# 24Vto320V.net
KiCad netlist of a schematic drawn in Altium Designer
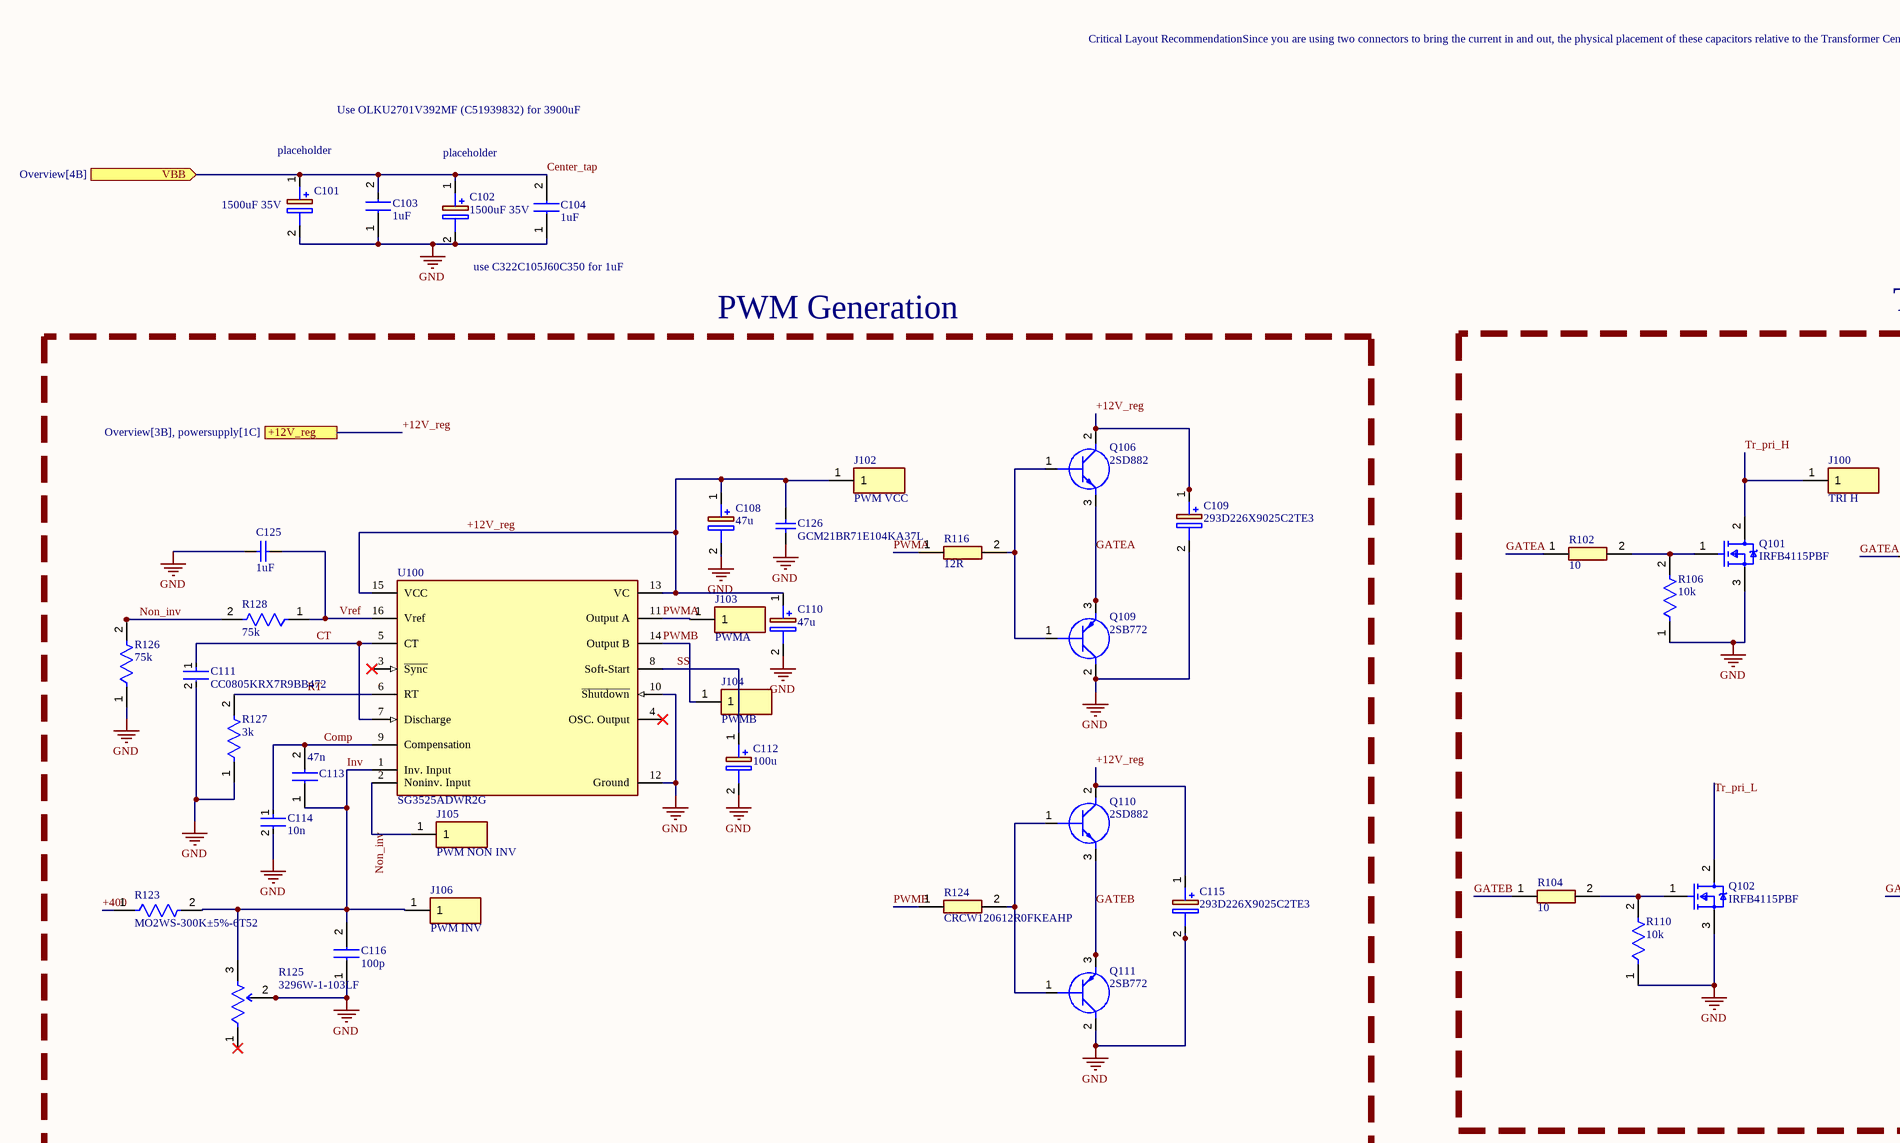
[diagram p0: 24Vto320V.SchDoc, top left]
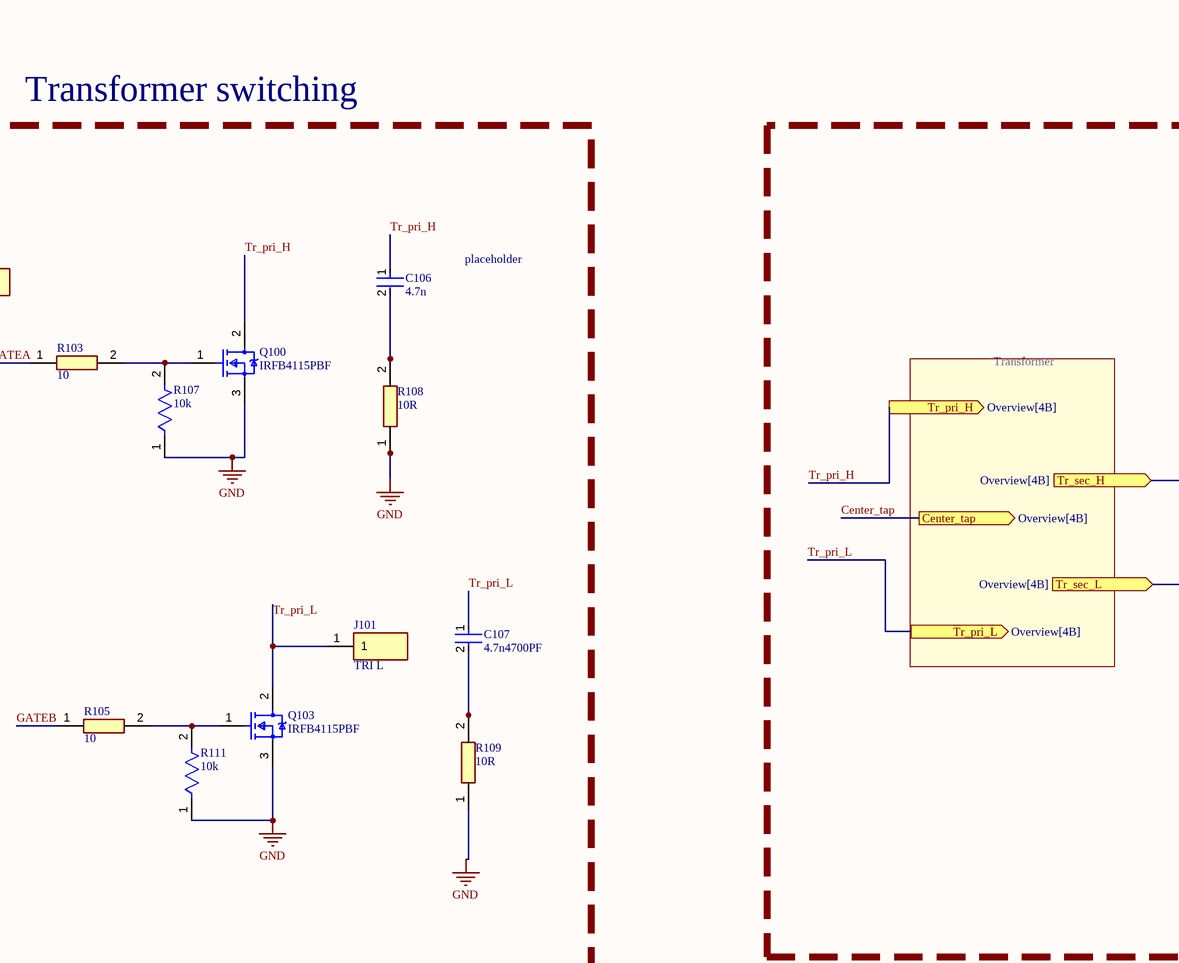
[diagram p1: 24Vto320V.SchDoc, top middle]
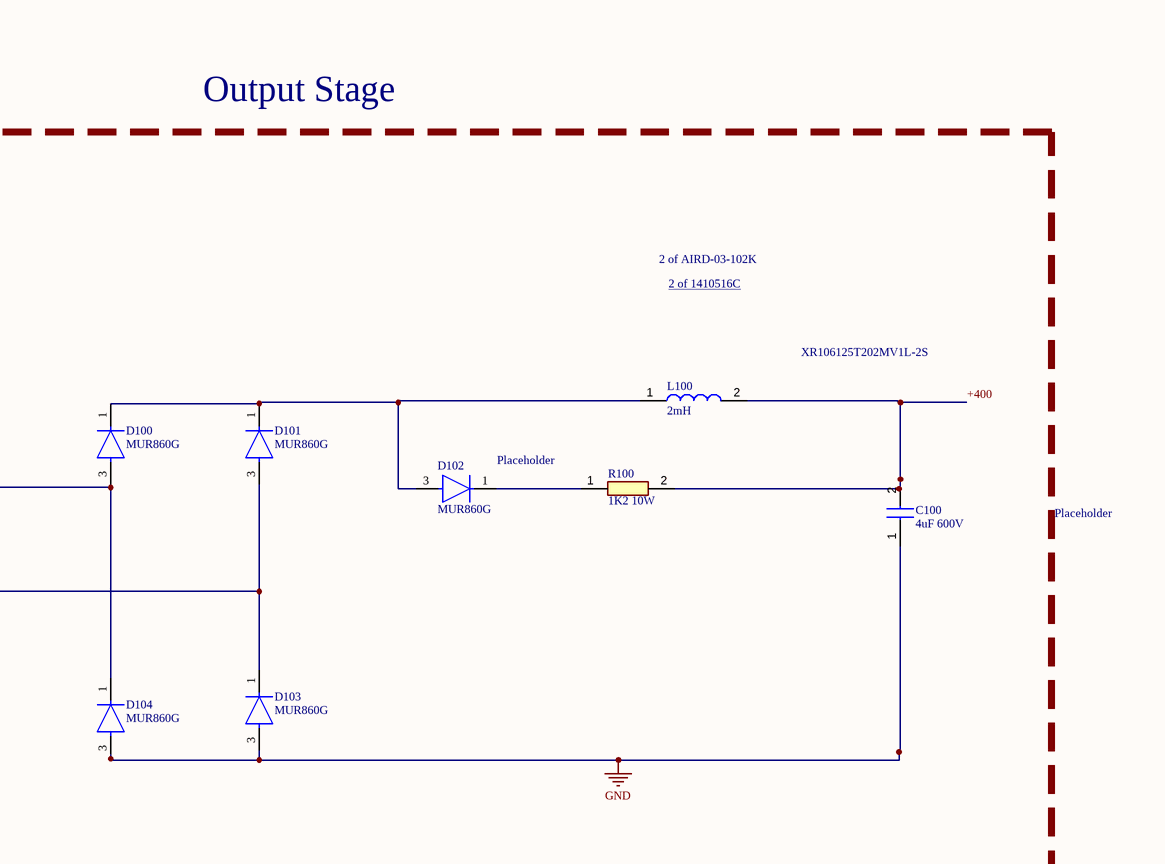
[diagram p2: 24Vto320V.SchDoc, top right]
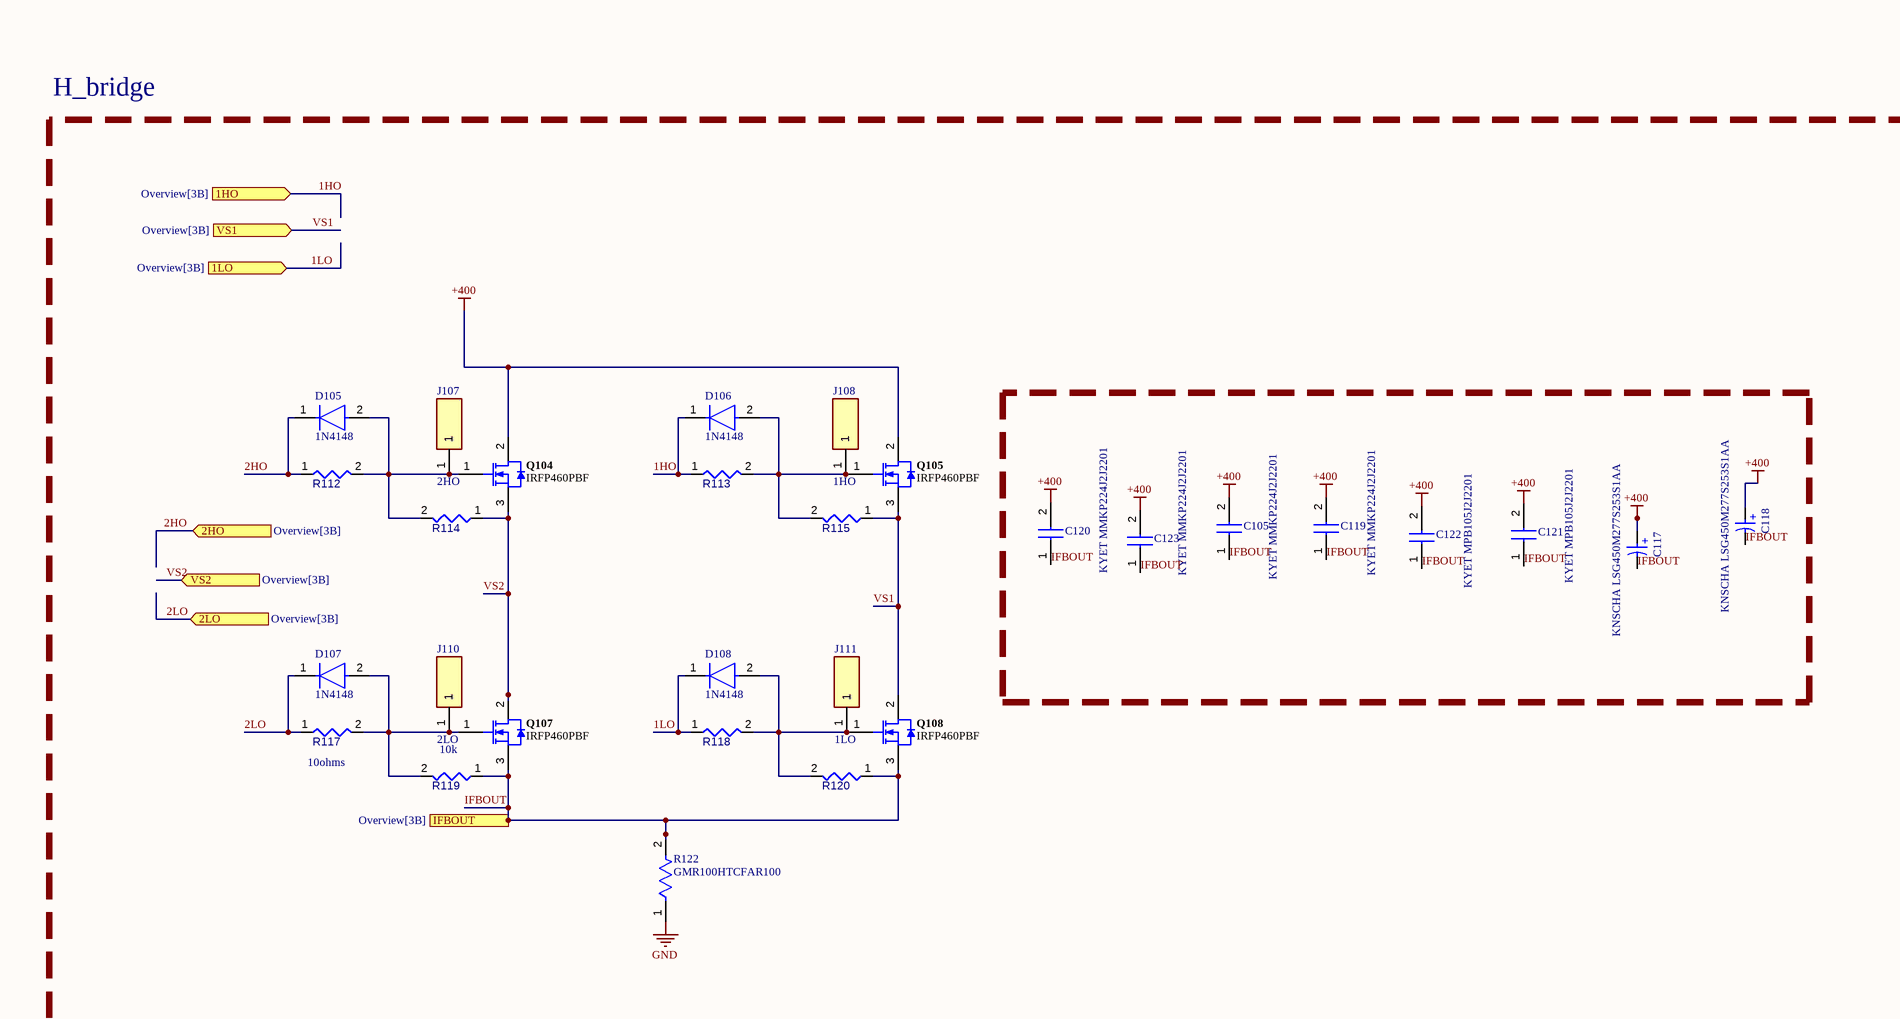
[diagram p3: 24Vto320V.SchDoc, bottom left]
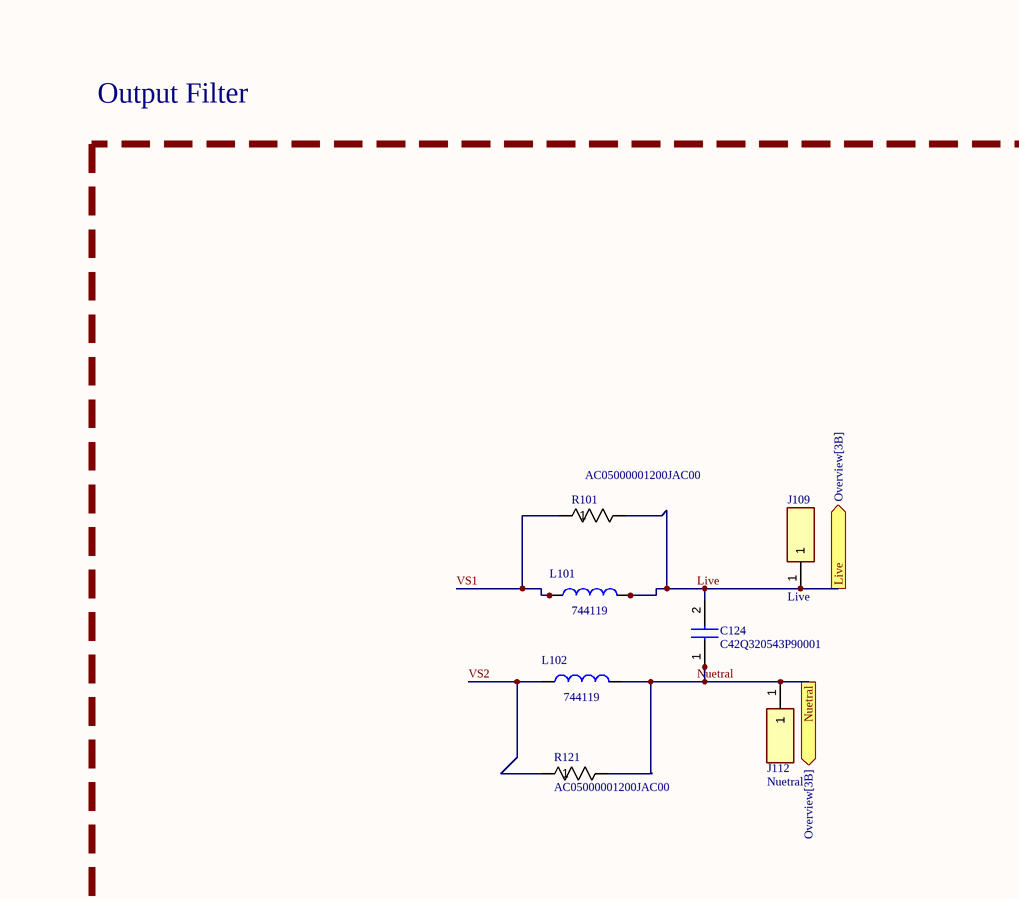
[diagram p4: 24Vto320V.SchDoc, bottom middle]

(export (version "E")
  (design (tool "Eeschema 10.0.6"))
  (components
    (comp (ref "C100")
      (value "4uF 600V")
      (footprint "SamacSys:ECWFE2J225P5")
      (description "C3D1U405KB00C00")
      (fields (field (name "MANUFACTURER_PART_NUMBER") "ECW-FE2J225P5"))
      (libsource (lib "SamacSys") (part "ECW-FE2J225P5"))
    )
    (comp (ref "C101")
      (value "1500uF 35V")
      (footprint "SamacSys:CAPPRD750W85D1800H2200")
      (description "35ZLH1500MEFC12.5X30")
      (fields
        (field (name "MANUFACTURER_PART_NUMBER") "EEU-FC1V152S")
        (field (name "MOUSER PART NUMBER") "667-EEU-FC1V152S")
      )
      (libsource (lib "*") (part "EEU-FC1V152S"))
    )
    (comp (ref "C102")
      (value "1500uF 35V")
      (footprint "SamacSys:CAPPRD750W85D1800H2200")
      (description "35ZLH1500MEFC12.5X30")
      (fields
        (field (name "MANUFACTURER_PART_NUMBER") "EEU-FC1V152S")
        (field (name "MOUSER PART NUMBER") "667-EEU-FC1V152S")
      )
      (libsource (lib "*") (part "EEU-FC1V152S"))
    )
    (comp (ref "C103")
      (value "1uF")
      (footprint "SamacSys:R75IN41004040J")
      (description "C322C105J60C350")
      (fields
        (field (name "MANUFACTURER_PART_NUMBER") "R75IN41004040J")
        (field (name "MOUSER PART NUMBER") "80-R75IN41004040J")
      )
      (libsource (lib "*") (part "R75IN41004040J"))
    )
    (comp (ref "C104")
      (value "1uF")
      (footprint "SamacSys:R75IN41004040J")
      (description "C322C105J60C350")
      (fields
        (field (name "MANUFACTURER_PART_NUMBER") "R75IN41004040J")
        (field (name "MOUSER PART NUMBER") "80-R75IN41004040J")
      )
      (libsource (lib "*") (part "R75IN41004040J"))
    )
    (comp (ref "C105")
      (value "KYET MMKP224J2J2201")
      (footprint "222233915224")
      (description "220nF Film Capacitor ±5% 630V Through Hole P=22.5mm")
      (fields (field (name "MANUFACTURER_PART_NUMBER") "222233915224"))
      (libsource (lib "myComponents") (part "222233915224"))
    )
    (comp (ref "C106")
      (value "4.7n")
      (footprint "FP-C1206C-EB-MFG")
      (description "CAP CER 4700PF 100V 10% X7R 1206\r\nCC1206KRX7R0BB472")
      (fields
        (field (name "TOLERANCE") "0.1")
        (field (name "OCTOPART") "https://octopart.com/c1206c472k1ractu-kemet-3865440")
      )
      (libsource (lib "Altium Content Vault") (part "b4654b650e69147ec39a6b967a45e02"))
    )
    (comp (ref "C107")
      (value "4.7n4700PF")
      (footprint "FP-C1206C-EB-MFG")
      (description "CAP CER 4700PF 100V 10% X7R 1206\r\nCC1206KRX7R0BB472")
      (fields
        (field (name "TOLERANCE") "0.1")
        (field (name "OCTOPART") "https://octopart.com/c1206c472k1ractu-kemet-3865440")
      )
      (libsource (lib "Altium Content Vault") (part "b4654b650e69147ec39a6b967a45e02"))
    )
    (comp (ref "C108")
      (value "47u")
      (footprint "SamacSys:CAPPRD250W55D655H1220")
      (description "EEU-FC1V470")
      (fields (field (name "MOUSER PART NUMBER") "667-EEU-FC1V470"))
      (libsource (lib "*") (part "EEU-FC1V470"))
    )
    (comp (ref "C109")
      (value "293D226X9025C2TE3")
      (footprint "CAPPM6032X280N")
      (description "Capacitor Polarised")
      (fields (field (name "MOUSER PART NUMBER") "74-293D226X9025C2TE3"))
      (libsource (lib "myComponents") (part "293D226X9025C2TE3"))
    )
    (comp (ref "C110")
      (value "47u")
      (footprint "SamacSys:CAPPRD250W55D655H1220")
      (description "EEU-FC1V470")
      (fields (field (name "MOUSER PART NUMBER") "667-EEU-FC1V470"))
      (libsource (lib "*") (part "EEU-FC1V470"))
    )
    (comp (ref "C111")
      (value "CC0805KRX7R9BB472")
      (footprint "FP-CC0805-0_85-MFG")
      (description "CAP CER 4700PF 50V X7R 0805")
      (fields (field (name "TOLERANCE") "0.1") (field (name "MANUFACTURER") "Yageo"))
      (libsource (lib "Altium Content Vault") (part "11868f565c42a9108669ba33697ecf6"))
    )
    (comp (ref "C112")
      (value "100u")
      (footprint "SamacSys:EEE0JA331XP")
      (description "EEE-1VA101XP")
      (fields (field (name "MOUSER PART NUMBER") "667-EEE-1VA101XP"))
      (libsource (lib "*") (part "EEE-1VA101XP"))
    )
    (comp (ref "C113")
      (value "47n")
      (footprint "SamacSys:CAPC2012X145N")
      (description "GRM21BR71H473KA01L")
      (fields (field (name "MOUSER PART NUMBER") "81-GRM40X473K50L"))
      (libsource (lib "*") (part "GRM21BR71H473KA01L"))
    )
    (comp (ref "C114")
      (value "10n")
      (footprint "FP-CC0805-0_85-MFG")
      (description "CAP CER 10000PF 50V X7R 0805\r\nCC0805KRX7R9BB103")
      (fields
        (field (name "OCTOPART") "https://octopart.com/cc0805krx7r9bb103-yageo-192989")
        (field (name "MANUFACTURER") "Yageo")
      )
      (libsource (lib "Altium Content Vault") (part "11868f565c42a9108669ba33697ecf6"))
    )
    (comp (ref "C115")
      (value "293D226X9025C2TE3")
      (footprint "CAPPM6032X280N")
      (description "Capacitor Polarised")
      (fields (field (name "MOUSER PART NUMBER") "74-293D226X9025C2TE3"))
      (libsource (lib "myComponents") (part "293D226X9025C2TE3"))
    )
    (comp (ref "C116")
      (value "100p")
      (footprint "SamacSys:CAPC3216X88N")
      (description "C1206C101J5GACTU7990")
      (libsource (lib "*") (part "C1206C101J5GACTU7990"))
    )
    (comp (ref "C117")
      (value "KNSCHA LSG450M277S253S1AA")
      (footprint "WCAP-AIG8_D30H30")
      (description "270uF ±20% 450V Aluminum Electrolytic Capacitors Through Hole,D30xL25mm")
      (fields (field (name "TOLERANCE") "20%"))
      (libsource (lib "Altium Content Vault") (part "Capacitor_Polarized"))
    )
    (comp (ref "C118")
      (value "KNSCHA LSG450M277S253S1AA")
      (footprint "WCAP-AIG8_D30H30")
      (description "270uF ±20% 450V Aluminum Electrolytic Capacitors Through Hole,D30xL25mm")
      (fields (field (name "TOLERANCE") "20%"))
      (libsource (lib "Altium Content Vault") (part "Capacitor_Polarized"))
    )
    (comp (ref "C119")
      (value "KYET MMKP224J2J2201")
      (footprint "222233915224")
      (description "220nF Film Capacitor ±5% 630V Through Hole P=22.5mm")
      (fields (field (name "MANUFACTURER_PART_NUMBER") "222233915224"))
      (libsource (lib "myComponents") (part "222233915224"))
    )
    (comp (ref "C120")
      (value "KYET MMKP224J2J2201")
      (footprint "222233915224")
      (description "220nF Film Capacitor ±5% 630V Through Hole P=22.5mm")
      (fields (field (name "MANUFACTURER_PART_NUMBER") "222233915224"))
      (libsource (lib "myComponents") (part "222233915224"))
    )
    (comp (ref "C121")
      (value "KYET MPB105J2J2201")
      (footprint "222233915224")
      (description "1uF Film Capacitor ±5% 630V Through Hole P=22.5mm")
      (fields (field (name "MANUFACTURER_PART_NUMBER") "222233915224"))
      (libsource (lib "myComponents") (part "222233915224"))
    )
    (comp (ref "C122")
      (value "KYET MPB105J2J2201")
      (footprint "222233915224")
      (description "1uF Film Capacitor ±5% 630V Through Hole P=22.5mm")
      (fields (field (name "MANUFACTURER_PART_NUMBER") "222233915224"))
      (libsource (lib "myComponents") (part "222233915224"))
    )
    (comp (ref "C123")
      (value "KYET MMKP224J2J2201")
      (footprint "222233915224")
      (description "220nF Film Capacitor ±5% 630V Through Hole P=22.5mm")
      (fields (field (name "MANUFACTURER_PART_NUMBER") "222233915224"))
      (libsource (lib "myComponents") (part "222233915224"))
    )
    (comp (ref "C124")
      (value "C42Q320543P90001")
      (footprint "222233915224")
      (description "2uF ±10% 275V 310V Safety Capacitor X2 Through Hole,P=22.5mm")
      (fields (field (name "MANUFACTURER_PART_NUMBER") "222233915224"))
      (libsource (lib "myComponents") (part "222233915224"))
    )
    (comp (ref "C125")
      (value "1uF")
      (footprint "CAPC2013X140X50LL20T25")
      (description "C0805C105K3RACTU")
      (fields (field (name "MANUFACTURER") "Kemet"))
      (libsource (lib "Altium Content Vault") (part "CAP"))
    )
    (comp (ref "C126")
      (value "GCM21BR71E104KA37L")
      (footprint "CAPC2013X140X45LL15T25")
      (fields (field (name "MANUFACTURER") "Murata"))
      (libsource (lib "Altium Content Vault") (part "CAP"))
    )
    (comp (ref "D100")
      (value "MUR860G")
      (footprint "FP-221B-04-MFG")
      (libsource (lib "Altium Content Vault") (part "40f15f7c8986038b0a9b2b5fe848ef9"))
    )
    (comp (ref "D101")
      (value "MUR860G")
      (footprint "FP-221B-04-MFG")
      (libsource (lib "Altium Content Vault") (part "40f15f7c8986038b0a9b2b5fe848ef9"))
    )
    (comp (ref "D102")
      (value "MUR860G")
      (footprint "FP-221B-04-MFG")
      (libsource (lib "Altium Content Vault") (part "40f15f7c8986038b0a9b2b5fe848ef9"))
    )
    (comp (ref "D103")
      (value "MUR860G")
      (footprint "FP-221B-04-MFG")
      (libsource (lib "Altium Content Vault") (part "40f15f7c8986038b0a9b2b5fe848ef9"))
    )
    (comp (ref "D104")
      (value "MUR860G")
      (footprint "FP-221B-04-MFG")
      (libsource (lib "Altium Content Vault") (part "40f15f7c8986038b0a9b2b5fe848ef9"))
    )
    (comp (ref "D105")
      (value "1N4148")
      (footprint "FP-017AG-MFG")
      (description "DIODE GEN PURP 100V 200MA DO35")
      (fields (field (name "VOLTAGE") "100V"))
      (libsource (lib "Altium Content Vault") (part "d7152d700b627762746794eb795d46e"))
    )
    (comp (ref "D106")
      (value "1N4148")
      (footprint "FP-017AG-MFG")
      (description "DIODE GEN PURP 100V 200MA DO35")
      (fields (field (name "VOLTAGE") "100V"))
      (libsource (lib "Altium Content Vault") (part "d7152d700b627762746794eb795d46e"))
    )
    (comp (ref "D107")
      (value "1N4148")
      (footprint "FP-017AG-MFG")
      (description "DIODE GEN PURP 100V 200MA DO35")
      (fields (field (name "VOLTAGE") "100V"))
      (libsource (lib "Altium Content Vault") (part "d7152d700b627762746794eb795d46e"))
    )
    (comp (ref "D108")
      (value "1N4148")
      (footprint "FP-017AG-MFG")
      (description "DIODE GEN PURP 100V 200MA DO35")
      (fields (field (name "VOLTAGE") "100V"))
      (libsource (lib "Altium Content Vault") (part "d7152d700b627762746794eb795d46e"))
    )
    (comp (ref "J100")
      (value "TRI H")
      (footprint "5000")
      (description "Connector")
      (fields (field (name "MANUFACTURER_PART_NUMBER") "5000") (field (name "MOUSER PART NUMBER") "534-5000"))
      (libsource (lib "myComponents") (part "5000"))
    )
    (comp (ref "J101")
      (value "TRI L")
      (footprint "5000")
      (description "Connector")
      (fields (field (name "MANUFACTURER_PART_NUMBER") "5000") (field (name "MOUSER PART NUMBER") "534-5000"))
      (libsource (lib "myComponents") (part "5000"))
    )
    (comp (ref "J102")
      (value "PWM VCC")
      (footprint "5000")
      (description "Connector")
      (fields (field (name "MANUFACTURER_PART_NUMBER") "5000") (field (name "MOUSER PART NUMBER") "534-5000"))
      (libsource (lib "myComponents") (part "5000"))
    )
    (comp (ref "J103")
      (value "PWMA")
      (footprint "5000")
      (description "Connector")
      (fields (field (name "MANUFACTURER_PART_NUMBER") "5000") (field (name "MOUSER PART NUMBER") "534-5000"))
      (libsource (lib "myComponents") (part "5000"))
    )
    (comp (ref "J104")
      (value "PWMB")
      (footprint "5000")
      (description "Connector")
      (fields (field (name "MANUFACTURER_PART_NUMBER") "5000") (field (name "MOUSER PART NUMBER") "534-5000"))
      (libsource (lib "myComponents") (part "5000"))
    )
    (comp (ref "J105")
      (value "PWM NON INV")
      (footprint "5000")
      (description "Connector")
      (fields (field (name "MANUFACTURER_PART_NUMBER") "5000") (field (name "MOUSER PART NUMBER") "534-5000"))
      (libsource (lib "myComponents") (part "5000"))
    )
    (comp (ref "J106")
      (value "PWM INV")
      (footprint "5000")
      (description "Connector")
      (fields (field (name "MANUFACTURER_PART_NUMBER") "5000") (field (name "MOUSER PART NUMBER") "534-5000"))
      (libsource (lib "myComponents") (part "5000"))
    )
    (comp (ref "J107")
      (value "2HO")
      (footprint "5000")
      (description "Connector")
      (fields (field (name "MANUFACTURER_PART_NUMBER") "5000") (field (name "MOUSER PART NUMBER") "534-5000"))
      (libsource (lib "") (part "5000_1"))
    )
    (comp (ref "J108")
      (value "1HO")
      (footprint "5000")
      (description "Connector")
      (fields (field (name "MANUFACTURER_PART_NUMBER") "5000") (field (name "MOUSER PART NUMBER") "534-5000"))
      (libsource (lib "") (part "5000_1"))
    )
    (comp (ref "J109")
      (value "Live")
      (footprint "5000")
      (description "Connector")
      (fields (field (name "MANUFACTURER_PART_NUMBER") "5000") (field (name "MOUSER PART NUMBER") "534-5000"))
      (libsource (lib "") (part "5000_1"))
    )
    (comp (ref "J110")
      (value "2LO")
      (footprint "5000")
      (description "Connector")
      (fields (field (name "MANUFACTURER_PART_NUMBER") "5000") (field (name "MOUSER PART NUMBER") "534-5000"))
      (libsource (lib "") (part "5000_1"))
    )
    (comp (ref "J111")
      (value "1LO")
      (footprint "5000")
      (description "Connector")
      (fields (field (name "MANUFACTURER_PART_NUMBER") "5000") (field (name "MOUSER PART NUMBER") "534-5000"))
      (libsource (lib "") (part "5000_1"))
    )
    (comp (ref "J112")
      (value "Nuetral")
      (footprint "5000")
      (description "Connector")
      (fields (field (name "MANUFACTURER_PART_NUMBER") "5000") (field (name "MOUSER PART NUMBER") "534-5000"))
      (libsource (lib "") (part "5000_2"))
    )
    (comp (ref "L100")
      (value "2mH")
      (footprint "SamacSys:2300LL102VRC")
      (description "XR106125T202MV1L-2S")
      (fields
        (field (name "MANUFACTURER_PART_NUMBER") "2300LL-102-V-RC")
        (field (name "MOUSER PART NUMBER") "652-2300LL-102-V-RC")
      )
      (libsource (lib "*") (part "2300LL-102-V-RC"))
    )
    (comp (ref "L101")
      (value "744119")
      (footprint "744119")
      (description "Toroidal Inductor, 890Uh, 2A, Tht Rohs Compliant: Yes")
      (fields (field (name "TOLERANCE") "20%"))
      (libsource (lib "Altium Content Vault") (part "Inductor - 1"))
    )
    (comp (ref "L102")
      (value "744119")
      (footprint "744119")
      (description "Toroidal Inductor, 890Uh, 2A, Tht Rohs Compliant: Yes")
      (fields (field (name "TOLERANCE") "20%"))
      (libsource (lib "Altium Content Vault") (part "Inductor - 1"))
    )
    (comp (ref "Q100")
      (value "IRFB4115PBF")
      (footprint "FP-PG-TO220-3-MFG")
      (description "MOSFET N-CH 150V 104A TO220AB")
      (fields
        (field (name "OCTOPART") "https://octopart.com/irfb4115pbf-infineon-65873822")
        (field (name "MANUFACTURER") "Infineon Technologies")
      )
      (libsource (lib "Altium Content Vault") (part "b09f7f152735e370c1ea22a33fa83d6"))
    )
    (comp (ref "Q101")
      (value "IRFB4115PBF")
      (footprint "FP-PG-TO220-3-MFG")
      (description "MOSFET N-CH 150V 104A TO220AB")
      (fields
        (field (name "OCTOPART") "https://octopart.com/irfb4115pbf-infineon-65873822")
        (field (name "MANUFACTURER") "Infineon Technologies")
      )
      (libsource (lib "Altium Content Vault") (part "b09f7f152735e370c1ea22a33fa83d6"))
    )
    (comp (ref "Q102")
      (value "IRFB4115PBF")
      (footprint "FP-PG-TO220-3-MFG")
      (description "MOSFET N-CH 150V 104A TO220AB")
      (fields
        (field (name "OCTOPART") "https://octopart.com/irfb4115pbf-infineon-65873822")
        (field (name "MANUFACTURER") "Infineon Technologies")
      )
      (libsource (lib "Altium Content Vault") (part "b09f7f152735e370c1ea22a33fa83d6"))
    )
    (comp (ref "Q103")
      (value "IRFB4115PBF")
      (footprint "FP-PG-TO220-3-MFG")
      (description "MOSFET N-CH 150V 104A TO220AB")
      (fields
        (field (name "OCTOPART") "https://octopart.com/irfb4115pbf-infineon-65873822")
        (field (name "MANUFACTURER") "Infineon Technologies")
      )
      (libsource (lib "Altium Content Vault") (part "b09f7f152735e370c1ea22a33fa83d6"))
    )
    (comp (ref "Q104")
      (value "IRFP460PBF")
      (footprint "VISH-TO-247AC-3")
      (description "N-Channel Power MOSFET, 500 V, -55 to 150 degC, 3-Pin FM (TO-247), RoHS, Tube")
      (fields (field (name "MANUFACTURER") "Vishay"))
      (libsource (lib "Altium Content Vault") (part "NEMOS-GDS-3"))
    )
    (comp (ref "Q105")
      (value "IRFP460PBF")
      (footprint "VISH-TO-247AC-3")
      (description "N-Channel Power MOSFET, 500 V, -55 to 150 degC, 3-Pin FM (TO-247), RoHS, Tube")
      (fields (field (name "MANUFACTURER") "Vishay"))
      (libsource (lib "Altium Content Vault") (part "NEMOS-GDS-3"))
    )
    (comp (ref "Q106")
      (value "2SD882")
      (footprint "SamacSys:BD235")
      (description "Transistor BJT NPN")
      (fields (field (name "MOUSER PART NUMBER") "511-2SD882"))
      (libsource (lib "*") (part "2SD882"))
    )
    (comp (ref "Q107")
      (value "IRFP460PBF")
      (footprint "VISH-TO-247AC-3")
      (description "N-Channel Power MOSFET, 500 V, -55 to 150 degC, 3-Pin FM (TO-247), RoHS, Tube")
      (fields (field (name "MANUFACTURER") "Vishay"))
      (libsource (lib "Altium Content Vault") (part "NEMOS-GDS-3"))
    )
    (comp (ref "Q108")
      (value "IRFP460PBF")
      (footprint "VISH-TO-247AC-3")
      (description "N-Channel Power MOSFET, 500 V, -55 to 150 degC, 3-Pin FM (TO-247), RoHS, Tube")
      (fields (field (name "MANUFACTURER") "Vishay"))
      (libsource (lib "Altium Content Vault") (part "NEMOS-GDS-3"))
    )
    (comp (ref "Q109")
      (value "2SB772")
      (footprint "SamacSys:TO229P290X760X1320-3P")
      (description "Transistor BJT PNP")
      (fields (field (name "MOUSER PART NUMBER") "511-2SB772"))
      (libsource (lib "*") (part "2SB772"))
    )
    (comp (ref "Q110")
      (value "2SD882")
      (footprint "SamacSys:BD235")
      (description "Transistor BJT NPN")
      (fields (field (name "MOUSER PART NUMBER") "511-2SD882"))
      (libsource (lib "*") (part "2SD882"))
    )
    (comp (ref "Q111")
      (value "2SB772")
      (footprint "SamacSys:TO229P290X760X1320-3P")
      (description "Transistor BJT PNP")
      (fields (field (name "MOUSER PART NUMBER") "511-2SB772"))
      (libsource (lib "*") (part "2SB772"))
    )
    (comp (ref "R100")
      (value "1K2 10W")
      (footprint "SamacSys:SQP10AJB100R")
      (description "SQP10AJB-1K2")
      (fields (field (name "MOUSER PART NUMBER") "603-SQP10AJB-1K2"))
      (libsource (lib "*") (part "SQP10AJB-1K2"))
    )
    (comp (ref "R101")
      (value "AC05000001200JAC00")
      (footprint "RES_AC05_VIS")
      (description "AC05000001200JAC00 Resistor, 120 Ohm, ± 5%, 5 W, Axial Leaded, Wirewound, General Purpose")
      (fields (field (name "TOLERANCE") "5%"))
      (libsource (lib "Altium Content Vault") (part "AC05000001200JAC00"))
    )
    (comp (ref "R102")
      (value "10")
      (footprint "SamacSys:RESC3216X60N")
      (description "CRCW120610R0FKEA")
      (fields (field (name "MOUSER PART NUMBER") "71-CRCW1206-10-E3"))
      (libsource (lib "*") (part "CRCW120610R0FKEA"))
    )
    (comp (ref "R103")
      (value "10")
      (footprint "SamacSys:RESC3216X60N")
      (description "CRCW120610R0FKEA")
      (fields (field (name "MOUSER PART NUMBER") "71-CRCW1206-10-E3"))
      (libsource (lib "*") (part "CRCW120610R0FKEA"))
    )
    (comp (ref "R104")
      (value "10")
      (footprint "SamacSys:RESC3216X60N")
      (description "CRCW120610R0FKEA")
      (fields (field (name "MOUSER PART NUMBER") "71-CRCW1206-10-E3"))
      (libsource (lib "*") (part "CRCW120610R0FKEA"))
    )
    (comp (ref "R105")
      (value "10")
      (footprint "SamacSys:RESC3216X60N")
      (description "CRCW120610R0FKEA")
      (fields (field (name "MOUSER PART NUMBER") "71-CRCW1206-10-E3"))
      (libsource (lib "*") (part "CRCW120610R0FKEA"))
    )
    (comp (ref "R106")
      (value "10k")
      (footprint "FP-CRCW0805-e3-IPC_A")
      (description "RES Thick Film, 10kΩ, 1%, 0.125W, 100ppm/°C, 0805, CRCW080510K0FKEA")
      (fields (field (name "TOLERANCE") "1%"))
      (libsource (lib "Altium Content Vault") (part "1029c3af85768c4190bb7ad29bc67b5"))
    )
    (comp (ref "R107")
      (value "10k")
      (footprint "FP-CRCW0805-e3-IPC_A")
      (description "RES Thick Film, 10kΩ, 1%, 0.125W, 100ppm/°C, 0805, CRCW080510K0FKEA")
      (fields (field (name "TOLERANCE") "1%"))
      (libsource (lib "Altium Content Vault") (part "1029c3af85768c4190bb7ad29bc67b5"))
    )
    (comp (ref "R108")
      (value "10R")
      (footprint "SamacSys:RESC6332X70N")
      (description "CRCW251210R0FKEG")
      (fields (field (name "MOUSER PART NUMBER") "71-CRCW2512-10-E3"))
      (libsource (lib "*") (part "CRCW251210R0FKEG"))
    )
    (comp (ref "R109")
      (value "10R")
      (footprint "SamacSys:RESC6332X70N")
      (description "CRCW251210R0FKEG")
      (fields (field (name "MOUSER PART NUMBER") "71-CRCW2512-10-E3"))
      (libsource (lib "*") (part "CRCW251210R0FKEG"))
    )
    (comp (ref "R110")
      (value "10k")
      (footprint "FP-CRCW0805-e3-IPC_A")
      (description "RES Thick Film, 10kΩ, 1%, 0.125W, 100ppm/°C, 0805, CRCW080510K0FKEA")
      (fields (field (name "TOLERANCE") "1%"))
      (libsource (lib "Altium Content Vault") (part "1029c3af85768c4190bb7ad29bc67b5"))
    )
    (comp (ref "R111")
      (value "10k")
      (footprint "FP-CRCW0805-e3-IPC_A")
      (description "RES Thick Film, 10kΩ, 1%, 0.125W, 100ppm/°C, 0805, CRCW080510K0FKEA")
      (fields (field (name "TOLERANCE") "1%"))
      (libsource (lib "Altium Content Vault") (part "1029c3af85768c4190bb7ad29bc67b5"))
    )
    (comp (ref "R112")
      (value "4.7 Ohm")
      (footprint "RESC0805(2012)_L")
      (description "4.7 Ohm 0.125W 5% 0805 (2012 Metric)  SMD")
      (fields (field (name "TOLERANCE") "5%") (field (name "POWER") "125mW"))
      (libsource (lib "Rahulb 23") (part "470R5J"))
    )
    (comp (ref "R113")
      (value "4.7 Ohm")
      (footprint "RESC0805(2012)_L")
      (description "4.7 Ohm 0.125W 5% 0805 (2012 Metric)  SMD")
      (fields (field (name "TOLERANCE") "5%") (field (name "POWER") "125mW"))
      (libsource (lib "Rahulb 23") (part "470R5J"))
    )
    (comp (ref "R114")
      (value "Resistor 10k +/-1% 0805 125 mW")
      (footprint "RESC2013X50X35ML15T15")
      (description "Chip Resistor, 10 KOhm, +/- 1%, 125 mW, -55 to 155 degC, 0805 (2012 Metric)")
      (fields (field (name "TOLERANCE") "1%") (field (name "POWER") "125mW"))
      (libsource (lib "Rahulb 23") (part "RES-2"))
    )
    (comp (ref "R115")
      (value "Resistor 10k +/-1% 0805 125 mW")
      (footprint "RESC2013X50X35ML15T15")
      (description "Chip Resistor, 10 KOhm, +/- 1%, 125 mW, -55 to 155 degC, 0805 (2012 Metric)")
      (fields (field (name "TOLERANCE") "1%") (field (name "POWER") "125mW"))
      (libsource (lib "Rahulb 23") (part "RES-2"))
    )
    (comp (ref "R116")
      (value "12R")
      (footprint "SamacSys:RESC3116X65N")
      (description "CRCW120612R0FKEAHP")
      (fields (field (name "MOUSER PART NUMBER") "71-CRCW120612R0FKEAH"))
      (libsource (lib "*") (part "CRCW120612R0FKEAHP"))
    )
    (comp (ref "R117")
      (value "4.7 Ohm")
      (footprint "RESC0805(2012)_L")
      (description "4.7 Ohm 0.125W 5% 0805 (2012 Metric)  SMD")
      (fields (field (name "TOLERANCE") "5%") (field (name "POWER") "125mW"))
      (libsource (lib "Rahulb 23") (part "470R5J"))
    )
    (comp (ref "R118")
      (value "4.7 Ohm")
      (footprint "RESC0805(2012)_L")
      (description "4.7 Ohm 0.125W 5% 0805 (2012 Metric)  SMD")
      (fields (field (name "TOLERANCE") "5%") (field (name "POWER") "125mW"))
      (libsource (lib "Rahulb 23") (part "470R5J"))
    )
    (comp (ref "R119")
      (value "Resistor 10k +/-1% 0805 125 mW")
      (footprint "RESC2013X50X35ML15T15")
      (description "Chip Resistor, 10 KOhm, +/- 1%, 125 mW, -55 to 155 degC, 0805 (2012 Metric)")
      (fields (field (name "TOLERANCE") "1%") (field (name "POWER") "125mW"))
      (libsource (lib "Rahulb 23") (part "RES-2"))
    )
    (comp (ref "R120")
      (value "Resistor 10k +/-1% 0805 125 mW")
      (footprint "RESC2013X50X35ML15T15")
      (description "Chip Resistor, 10 KOhm, +/- 1%, 125 mW, -55 to 155 degC, 0805 (2012 Metric)")
      (fields (field (name "TOLERANCE") "1%") (field (name "POWER") "125mW"))
      (libsource (lib "Rahulb 23") (part "RES-2"))
    )
    (comp (ref "R121")
      (value "AC05000001200JAC00")
      (footprint "RES_AC05_VIS")
      (description "AC05000001200JAC00 Resistor, 120 Ohm, ± 5%, 5 W, Axial Leaded, Wirewound, General Purpose")
      (fields (field (name "TOLERANCE") "5%"))
      (libsource (lib "Altium Content Vault") (part "AC05000001200JAC00"))
    )
    (comp (ref "R122")
      (value "GMR100HTCFAR100")
      (footprint "FP-GMR100-MFG")
      (description "RES 0.1 OHM 1% 7W 2512")
      (fields (field (name "TOLERANCE") "1%"))
      (libsource (lib "Altium Content Vault") (part "1029c3af85768c4190bb7ad29bc67b5"))
    )
    (comp (ref "R123")
      (value "MO2WS-300K±5%-6T52")
      (footprint "FP-VR37-MFG")
      (description "RES 300k OHM 5% 1/2W AXIAL")
      (fields (field (name "TOLERANCE") "5%"))
      (libsource (lib "Altium Content Vault") (part "1029c3af85768c4190bb7ad29bc67b5"))
    )
    (comp (ref "R124")
      (value "CRCW120612R0FKEAHP")
      (footprint "SamacSys:RESC3116X65N")
      (description "Resistor")
      (fields (field (name "MOUSER PART NUMBER") "71-CRCW120612R0FKEAH"))
      (libsource (lib "*") (part "CRCW120612R0FKEAHP"))
    )
    (comp (ref "R125")
      (value "3296W-1-103LF")
      (footprint "FP-3296W-MFG")
      (description "TRIMMER 10K OHM 0.5W PC PIN TOP")
      (fields (field (name "TOLERANCE") "10%"))
      (libsource (lib "Altium Content Vault") (part "2dcfd2547301a7d3209a5e99acfd772"))
    )
    (comp (ref "R126")
      (value "75k")
      (footprint "FP-CRCW0805-e3-IPC_A")
      (description "RES Thick Film, 75kΩ, 1%, 0.125W, 100ppm/°C, 0805\r\nCRCW080575K0FKEA\r\nCRCW080575K0FKEA")
      (fields (field (name "TOLERANCE") "1%"))
      (libsource (lib "Altium Content Vault") (part "1029c3af85768c4190bb7ad29bc67b5"))
    )
    (comp (ref "R127")
      (value "3k")
      (footprint "FP-CRCW0805-e3-IPC_C")
      (description "RES Thick Film, 3kΩ, 1%, 0.125W, 100ppm/°C, 0805\r\nCRCW08053K00FKEA")
      (fields (field (name "TOLERANCE") "1%"))
      (libsource (lib "Altium Content Vault") (part "1029c3af85768c4190bb7ad29bc67b5"))
    )
    (comp (ref "R128")
      (value "75k")
      (footprint "FP-CRCW0805-e3-IPC_A")
      (description "RES Thick Film, 75kΩ, 1%, 0.125W, 100ppm/°C, 0805\r\nCRCW080575K0FKEA\r\nCRCW080575K0FKEA")
      (fields (field (name "TOLERANCE") "1%"))
      (libsource (lib "Altium Content Vault") (part "1029c3af85768c4190bb7ad29bc67b5"))
    )
    (comp (ref "U100")
      (value "SG3525ADWR2G")
      (footprint "FP-751G-MFG")
      (libsource (lib "Altium Content Vault") (part "36a9b316f323cd2eebec0c7cb4c33a2"))
    )
  )
  (nets
    (net (code "1") (name "+400") (class "Default")
      (node (ref "C100") (pin "2") (pinfunction "2_2") (pintype "passive"))
      (node (ref "C105") (pin "2") (pinfunction "2_2") (pintype "passive"))
      (node (ref "C117") (pin "1") (pinfunction "P_1") (pintype "passive"))
      (node (ref "C118") (pin "1") (pinfunction "P_1") (pintype "passive"))
      (node (ref "C119") (pin "2") (pinfunction "2_2") (pintype "passive"))
      (node (ref "C120") (pin "2") (pinfunction "2_2") (pintype "passive"))
      (node (ref "C121") (pin "2") (pinfunction "2_2") (pintype "passive"))
      (node (ref "C122") (pin "2") (pinfunction "2_2") (pintype "passive"))
      (node (ref "C123") (pin "2") (pinfunction "2_2") (pintype "passive"))
      (node (ref "L100") (pin "2") (pinfunction "2_2") (pintype "passive"))
      (node (ref "Q104") (pin "2") (pinfunction "D_2") (pintype "passive"))
      (node (ref "Q105") (pin "2") (pinfunction "D_2") (pintype "passive"))
      (node (ref "R100") (pin "2") (pinfunction "2_2") (pintype "passive"))
      (node (ref "R123") (pin "1") (pinfunction "1_1") (pintype "passive"))
    )
    (net (code "2") (name "/+12V_reg") (class "Default")
      (node (ref "C108") (pin "1") (pinfunction "+_1") (pintype "passive"))
      (node (ref "C109") (pin "1") (pinfunction "+_1") (pintype "passive"))
      (node (ref "C110") (pin "1") (pinfunction "+_1") (pintype "passive"))
      (node (ref "C115") (pin "1") (pinfunction "+_1") (pintype "passive"))
      (node (ref "C126") (pin "2") (pinfunction "2_2") (pintype "passive"))
      (node (ref "J102") (pin "1") (pinfunction "1_1") (pintype "passive"))
      (node (ref "Q106") (pin "2") (pinfunction "C_2") (pintype "passive"))
      (node (ref "Q110") (pin "2") (pinfunction "C_2") (pintype "passive"))
      (node (ref "U100") (pin "13") (pinfunction "VC_13") (pintype "power_in"))
      (node (ref "U100") (pin "15") (pinfunction "VCC_15") (pintype "power_in"))
    )
    (net (code "3") (name "/1HO") (class "Default")
      (node (ref "D106") (pin "1") (pinfunction "C_1") (pintype "passive"))
      (node (ref "R113") (pin "1") (pinfunction "1_1") (pintype "passive"))
    )
    (net (code "4") (name "/1LO") (class "Default")
      (node (ref "D108") (pin "1") (pinfunction "C_1") (pintype "passive"))
      (node (ref "R118") (pin "1") (pinfunction "1_1") (pintype "passive"))
    )
    (net (code "5") (name "/2HO") (class "Default")
      (node (ref "D105") (pin "1") (pinfunction "C_1") (pintype "passive"))
      (node (ref "R112") (pin "1") (pinfunction "1_1") (pintype "passive"))
    )
    (net (code "6") (name "/2LO") (class "Default")
      (node (ref "D107") (pin "1") (pinfunction "C_1") (pintype "passive"))
      (node (ref "R117") (pin "1") (pinfunction "1_1") (pintype "passive"))
    )
    (net (code "7") (name "/CT") (class "Default")
      (node (ref "C111") (pin "1") (pinfunction "1_1") (pintype "passive"))
      (node (ref "U100") (pin "5") (pinfunction "CT_5") (pintype "passive"))
      (node (ref "U100") (pin "7") (pinfunction "Discharge_7") (pintype "input"))
    )
    (net (code "8") (name "/Center_tap") (class "Default")
      (node (ref "C101") (pin "1") (pinfunction "+_1") (pintype "passive"))
      (node (ref "C102") (pin "1") (pinfunction "+_1") (pintype "passive"))
      (node (ref "C103") (pin "2") (pinfunction "2_2") (pintype "passive"))
      (node (ref "C104") (pin "2") (pinfunction "2_2") (pintype "passive"))
    )
    (net (code "9") (name "/Comp") (class "Default")
      (node (ref "C113") (pin "2") (pinfunction "2_2") (pintype "passive"))
      (node (ref "C114") (pin "1") (pinfunction "1_1") (pintype "passive"))
      (node (ref "U100") (pin "9") (pinfunction "Compensation_9") (pintype "passive"))
    )
    (net (code "10") (name "/GATEA") (class "Default")
      (node (ref "Q106") (pin "3") (pinfunction "E_3") (pintype "passive"))
      (node (ref "Q109") (pin "3") (pinfunction "E_3") (pintype "passive"))
      (node (ref "R102") (pin "1") (pinfunction "1_1") (pintype "passive"))
      (node (ref "R103") (pin "1") (pinfunction "1_1") (pintype "passive"))
    )
    (net (code "11") (name "/GATEB") (class "Default")
      (node (ref "Q110") (pin "3") (pinfunction "E_3") (pintype "passive"))
      (node (ref "Q111") (pin "3") (pinfunction "E_3") (pintype "passive"))
      (node (ref "R104") (pin "1") (pinfunction "1_1") (pintype "passive"))
      (node (ref "R105") (pin "1") (pinfunction "1_1") (pintype "passive"))
    )
    (net (code "12") (name "/IFBOUT") (class "Default")
      (node (ref "C105") (pin "1") (pinfunction "1_1") (pintype "passive"))
      (node (ref "C117") (pin "2") (pinfunction "N_2") (pintype "passive"))
      (node (ref "C118") (pin "2") (pinfunction "N_2") (pintype "passive"))
      (node (ref "C119") (pin "1") (pinfunction "1_1") (pintype "passive"))
      (node (ref "C120") (pin "1") (pinfunction "1_1") (pintype "passive"))
      (node (ref "C121") (pin "1") (pinfunction "1_1") (pintype "passive"))
      (node (ref "C122") (pin "1") (pinfunction "1_1") (pintype "passive"))
      (node (ref "C123") (pin "1") (pinfunction "1_1") (pintype "passive"))
      (node (ref "Q107") (pin "3") (pinfunction "S_3") (pintype "passive"))
      (node (ref "Q108") (pin "3") (pinfunction "S_3") (pintype "passive"))
      (node (ref "R119") (pin "1") (pinfunction "1_1") (pintype "passive"))
      (node (ref "R120") (pin "1") (pinfunction "1_1") (pintype "passive"))
      (node (ref "R122") (pin "2") (pinfunction "2_2") (pintype "passive"))
    )
    (net (code "13") (name "/Inv") (class "Default")
      (node (ref "C113") (pin "1") (pinfunction "1_1") (pintype "passive"))
      (node (ref "C116") (pin "2") (pinfunction "2_2") (pintype "passive"))
      (node (ref "J106") (pin "1") (pinfunction "1_1") (pintype "passive"))
      (node (ref "R123") (pin "2") (pinfunction "2_2") (pintype "passive"))
      (node (ref "R125") (pin "3") (pinfunction "CW_3") (pintype "passive"))
      (node (ref "U100") (pin "1") (pinfunction "Inv._Input_1") (pintype "tri_state"))
    )
    (net (code "14") (name "/Live") (class "Default")
      (node (ref "C124") (pin "2") (pinfunction "2_2") (pintype "passive"))
      (node (ref "J109") (pin "1") (pinfunction "1_1") (pintype "passive"))
      (node (ref "L101") (pin "2") (pinfunction "2_2") (pintype "passive"))
      (node (ref "R101") (pin "2") (pinfunction "2_2") (pintype "passive"))
    )
    (net (code "15") (name "/Non_inv") (class "Default")
      (node (ref "J105") (pin "1") (pinfunction "1_1") (pintype "passive"))
      (node (ref "R126") (pin "2") (pinfunction "2_2") (pintype "passive"))
      (node (ref "R128") (pin "2") (pinfunction "2_2") (pintype "passive"))
      (node (ref "U100") (pin "2") (pinfunction "Noninv._Input_2") (pintype "tri_state"))
    )
    (net (code "16") (name "/Nuetral") (class "Default")
      (node (ref "C124") (pin "1") (pinfunction "1_1") (pintype "passive"))
      (node (ref "J112") (pin "1") (pinfunction "1_1") (pintype "passive"))
      (node (ref "L102") (pin "2") (pinfunction "2_2") (pintype "passive"))
      (node (ref "R121") (pin "2") (pinfunction "2_2") (pintype "passive"))
    )
    (net (code "17") (name "/PWMA") (class "Default")
      (node (ref "J103") (pin "1") (pinfunction "1_1") (pintype "passive"))
      (node (ref "R116") (pin "1") (pinfunction "1_1") (pintype "passive"))
      (node (ref "U100") (pin "11") (pinfunction "Output_A_11") (pintype "passive"))
    )
    (net (code "18") (name "/PWMB") (class "Default")
      (node (ref "J104") (pin "1") (pinfunction "1_1") (pintype "passive"))
      (node (ref "R124") (pin "1") (pinfunction "1_1") (pintype "passive"))
      (node (ref "U100") (pin "14") (pinfunction "Output_B_14") (pintype "passive"))
    )
    (net (code "19") (name "/RT") (class "Default")
      (node (ref "R127") (pin "2") (pinfunction "2_2") (pintype "passive"))
      (node (ref "U100") (pin "6") (pinfunction "RT_6") (pintype "passive"))
    )
    (net (code "20") (name "/SS") (class "Default")
      (node (ref "C112") (pin "1") (pinfunction "+_1") (pintype "passive"))
      (node (ref "U100") (pin "8") (pinfunction "Soft-Start_8") (pintype "passive"))
    )
    (net (code "21") (name "/Tr_pri_H") (class "Default")
      (node (ref "C106") (pin "1") (pinfunction "1_1") (pintype "passive"))
      (node (ref "J100") (pin "1") (pinfunction "1_1") (pintype "passive"))
      (node (ref "Q100") (pin "2") (pinfunction "D_2") (pintype "passive"))
      (node (ref "Q101") (pin "2") (pinfunction "D_2") (pintype "passive"))
    )
    (net (code "22") (name "/Tr_pri_L") (class "Default")
      (node (ref "C107") (pin "1") (pinfunction "1_1") (pintype "passive"))
      (node (ref "J101") (pin "1") (pinfunction "1_1") (pintype "passive"))
      (node (ref "Q102") (pin "2") (pinfunction "D_2") (pintype "passive"))
      (node (ref "Q103") (pin "2") (pinfunction "D_2") (pintype "passive"))
    )
    (net (code "23") (name "/Tr_sec_H") (class "Default")
      (node (ref "D100") (pin "3") (pinfunction "A_3") (pintype "passive"))
      (node (ref "D104") (pin "1") (pinfunction "C_1") (pintype "passive"))
    )
    (net (code "24") (name "/Tr_sec_L") (class "Default")
      (node (ref "D101") (pin "3") (pinfunction "A_3") (pintype "passive"))
      (node (ref "D103") (pin "1") (pinfunction "C_1") (pintype "passive"))
    )
    (net (code "25") (name "/VS1") (class "Default")
      (node (ref "L101") (pin "1") (pinfunction "1_1") (pintype "passive"))
      (node (ref "Q105") (pin "3") (pinfunction "S_3") (pintype "passive"))
      (node (ref "Q108") (pin "2") (pinfunction "D_2") (pintype "passive"))
      (node (ref "R101") (pin "1") (pinfunction "1_1") (pintype "passive"))
      (node (ref "R115") (pin "1") (pinfunction "1_1") (pintype "passive"))
    )
    (net (code "26") (name "/VS2") (class "Default")
      (node (ref "L102") (pin "1") (pinfunction "1_1") (pintype "passive"))
      (node (ref "Q104") (pin "3") (pinfunction "S_3") (pintype "passive"))
      (node (ref "Q107") (pin "2") (pinfunction "D_2") (pintype "passive"))
      (node (ref "R114") (pin "1") (pinfunction "1_1") (pintype "passive"))
      (node (ref "R121") (pin "1") (pinfunction "1_1") (pintype "passive"))
    )
    (net (code "27") (name "/Vref") (class "Default")
      (node (ref "C125") (pin "1") (pinfunction "1_1") (pintype "passive"))
      (node (ref "R128") (pin "1") (pinfunction "1_1") (pintype "passive"))
      (node (ref "U100") (pin "16") (pinfunction "Vref_16") (pintype "passive"))
    )
    (net (code "28") (name "GND") (class "Default")
      (node (ref "C100") (pin "1") (pinfunction "1_1") (pintype "passive"))
      (node (ref "C101") (pin "2") (pinfunction "-_2") (pintype "passive"))
      (node (ref "C102") (pin "2") (pinfunction "-_2") (pintype "passive"))
      (node (ref "C103") (pin "1") (pinfunction "1_1") (pintype "passive"))
      (node (ref "C104") (pin "1") (pinfunction "1_1") (pintype "passive"))
      (node (ref "C108") (pin "2") (pinfunction "-_2") (pintype "passive"))
      (node (ref "C109") (pin "2") (pinfunction "-_2") (pintype "passive"))
      (node (ref "C110") (pin "2") (pinfunction "-_2") (pintype "passive"))
      (node (ref "C111") (pin "2") (pinfunction "2_2") (pintype "passive"))
      (node (ref "C112") (pin "2") (pinfunction "-_2") (pintype "passive"))
      (node (ref "C114") (pin "2") (pinfunction "2_2") (pintype "passive"))
      (node (ref "C115") (pin "2") (pinfunction "-_2") (pintype "passive"))
      (node (ref "C116") (pin "1") (pinfunction "1_1") (pintype "passive"))
      (node (ref "C125") (pin "2") (pinfunction "2_2") (pintype "passive"))
      (node (ref "C126") (pin "1") (pinfunction "1_1") (pintype "passive"))
      (node (ref "D103") (pin "3") (pinfunction "A_3") (pintype "passive"))
      (node (ref "D104") (pin "3") (pinfunction "A_3") (pintype "passive"))
      (node (ref "Q100") (pin "3") (pinfunction "S_3") (pintype "passive"))
      (node (ref "Q101") (pin "3") (pinfunction "S_3") (pintype "passive"))
      (node (ref "Q102") (pin "3") (pinfunction "S_3") (pintype "passive"))
      (node (ref "Q103") (pin "3") (pinfunction "S_3") (pintype "passive"))
      (node (ref "Q109") (pin "2") (pinfunction "C_2") (pintype "passive"))
      (node (ref "Q111") (pin "2") (pinfunction "C_2") (pintype "passive"))
      (node (ref "R106") (pin "1") (pinfunction "1_1") (pintype "passive"))
      (node (ref "R107") (pin "1") (pinfunction "1_1") (pintype "passive"))
      (node (ref "R108") (pin "1") (pinfunction "1_1") (pintype "passive"))
      (node (ref "R109") (pin "1") (pinfunction "1_1") (pintype "passive"))
      (node (ref "R110") (pin "1") (pinfunction "1_1") (pintype "passive"))
      (node (ref "R111") (pin "1") (pinfunction "1_1") (pintype "passive"))
      (node (ref "R122") (pin "1") (pinfunction "1_1") (pintype "passive"))
      (node (ref "R125") (pin "2") (pinfunction "WIPER_2") (pintype "passive"))
      (node (ref "R126") (pin "1") (pinfunction "1_1") (pintype "passive"))
      (node (ref "R127") (pin "1") (pinfunction "1_1") (pintype "passive"))
      (node (ref "U100") (pin "10") (pinfunction "~{Shutdown}_10") (pintype "input"))
      (node (ref "U100") (pin "12") (pinfunction "Ground_12") (pintype "power_in"))
    )
    (net (code "29") (name "Net-(C106-Pad2)") (class "Default")
      (node (ref "C106") (pin "2") (pinfunction "2_2") (pintype "passive"))
      (node (ref "R108") (pin "2") (pinfunction "2_2") (pintype "passive"))
    )
    (net (code "30") (name "Net-(C107-Pad2)") (class "Default")
      (node (ref "C107") (pin "2") (pinfunction "2_2") (pintype "passive"))
      (node (ref "R109") (pin "2") (pinfunction "2_2") (pintype "passive"))
    )
    (net (code "31") (name "Net-(D100-C)") (class "Default")
      (node (ref "D100") (pin "1") (pinfunction "C_1") (pintype "passive"))
      (node (ref "D101") (pin "1") (pinfunction "C_1") (pintype "passive"))
      (node (ref "D102") (pin "3") (pinfunction "A_3") (pintype "passive"))
      (node (ref "L100") (pin "1") (pinfunction "1_1") (pintype "passive"))
    )
    (net (code "32") (name "Net-(D102-C)") (class "Default")
      (node (ref "D102") (pin "1") (pinfunction "C_1") (pintype "passive"))
      (node (ref "R100") (pin "1") (pinfunction "1_1") (pintype "passive"))
    )
    (net (code "33") (name "Net-(D105-A)") (class "Default")
      (node (ref "D105") (pin "2") (pinfunction "A_2") (pintype "passive"))
      (node (ref "J107") (pin "1") (pinfunction "1_1") (pintype "passive"))
      (node (ref "Q104") (pin "1") (pinfunction "G_1") (pintype "passive"))
      (node (ref "R112") (pin "2") (pinfunction "2_2") (pintype "passive"))
      (node (ref "R114") (pin "2") (pinfunction "2_2") (pintype "passive"))
    )
    (net (code "34") (name "Net-(D106-A)") (class "Default")
      (node (ref "D106") (pin "2") (pinfunction "A_2") (pintype "passive"))
      (node (ref "J108") (pin "1") (pinfunction "1_1") (pintype "passive"))
      (node (ref "Q105") (pin "1") (pinfunction "G_1") (pintype "passive"))
      (node (ref "R113") (pin "2") (pinfunction "2_2") (pintype "passive"))
      (node (ref "R115") (pin "2") (pinfunction "2_2") (pintype "passive"))
    )
    (net (code "35") (name "Net-(D107-A)") (class "Default")
      (node (ref "D107") (pin "2") (pinfunction "A_2") (pintype "passive"))
      (node (ref "J110") (pin "1") (pinfunction "1_1") (pintype "passive"))
      (node (ref "Q107") (pin "1") (pinfunction "G_1") (pintype "passive"))
      (node (ref "R117") (pin "2") (pinfunction "2_2") (pintype "passive"))
      (node (ref "R119") (pin "2") (pinfunction "2_2") (pintype "passive"))
    )
    (net (code "36") (name "Net-(D108-A)") (class "Default")
      (node (ref "D108") (pin "2") (pinfunction "A_2") (pintype "passive"))
      (node (ref "J111") (pin "1") (pinfunction "1_1") (pintype "passive"))
      (node (ref "Q108") (pin "1") (pinfunction "G_1") (pintype "passive"))
      (node (ref "R118") (pin "2") (pinfunction "2_2") (pintype "passive"))
      (node (ref "R120") (pin "2") (pinfunction "2_2") (pintype "passive"))
    )
    (net (code "37") (name "Net-(Q100-G)") (class "Default")
      (node (ref "Q100") (pin "1") (pinfunction "G_1") (pintype "passive"))
      (node (ref "R103") (pin "2") (pinfunction "2_2") (pintype "passive"))
      (node (ref "R107") (pin "2") (pinfunction "2_2") (pintype "passive"))
    )
    (net (code "38") (name "Net-(Q101-G)") (class "Default")
      (node (ref "Q101") (pin "1") (pinfunction "G_1") (pintype "passive"))
      (node (ref "R102") (pin "2") (pinfunction "2_2") (pintype "passive"))
      (node (ref "R106") (pin "2") (pinfunction "2_2") (pintype "passive"))
    )
    (net (code "39") (name "Net-(Q102-G)") (class "Default")
      (node (ref "Q102") (pin "1") (pinfunction "G_1") (pintype "passive"))
      (node (ref "R104") (pin "2") (pinfunction "2_2") (pintype "passive"))
      (node (ref "R110") (pin "2") (pinfunction "2_2") (pintype "passive"))
    )
    (net (code "40") (name "Net-(Q103-G)") (class "Default")
      (node (ref "Q103") (pin "1") (pinfunction "G_1") (pintype "passive"))
      (node (ref "R105") (pin "2") (pinfunction "2_2") (pintype "passive"))
      (node (ref "R111") (pin "2") (pinfunction "2_2") (pintype "passive"))
    )
    (net (code "41") (name "Net-(Q106-B)") (class "Default")
      (node (ref "Q106") (pin "1") (pinfunction "B_1") (pintype "passive"))
      (node (ref "Q109") (pin "1") (pinfunction "B_1") (pintype "passive"))
      (node (ref "R116") (pin "2") (pinfunction "2_2") (pintype "passive"))
    )
    (net (code "42") (name "Net-(Q110-B)") (class "Default")
      (node (ref "Q110") (pin "1") (pinfunction "B_1") (pintype "passive"))
      (node (ref "Q111") (pin "1") (pinfunction "B_1") (pintype "passive"))
      (node (ref "R124") (pin "2") (pinfunction "2_2") (pintype "passive"))
    )
    (net (code "43") (name "unconnected-(R125-CCW-Pad1)") (class "Default")
      (node (ref "R125") (pin "1") (pinfunction "CCW_1") (pintype "passive+no_connect"))
    )
    (net (code "44") (name "unconnected-(U100-OSC._Output-Pad4)") (class "Default")
      (node (ref "U100") (pin "4") (pinfunction "OSC._Output_4") (pintype "passive+no_connect"))
    )
    (net (code "45") (name "unconnected-(U100-~{Sync}-Pad3)") (class "Default")
      (node (ref "U100") (pin "3") (pinfunction "~{Sync}_3") (pintype "input+no_connect"))
    )
  )
)
